# FMC_ADC_top.net
KiCad netlist of a schematic drawn in Altium Designer
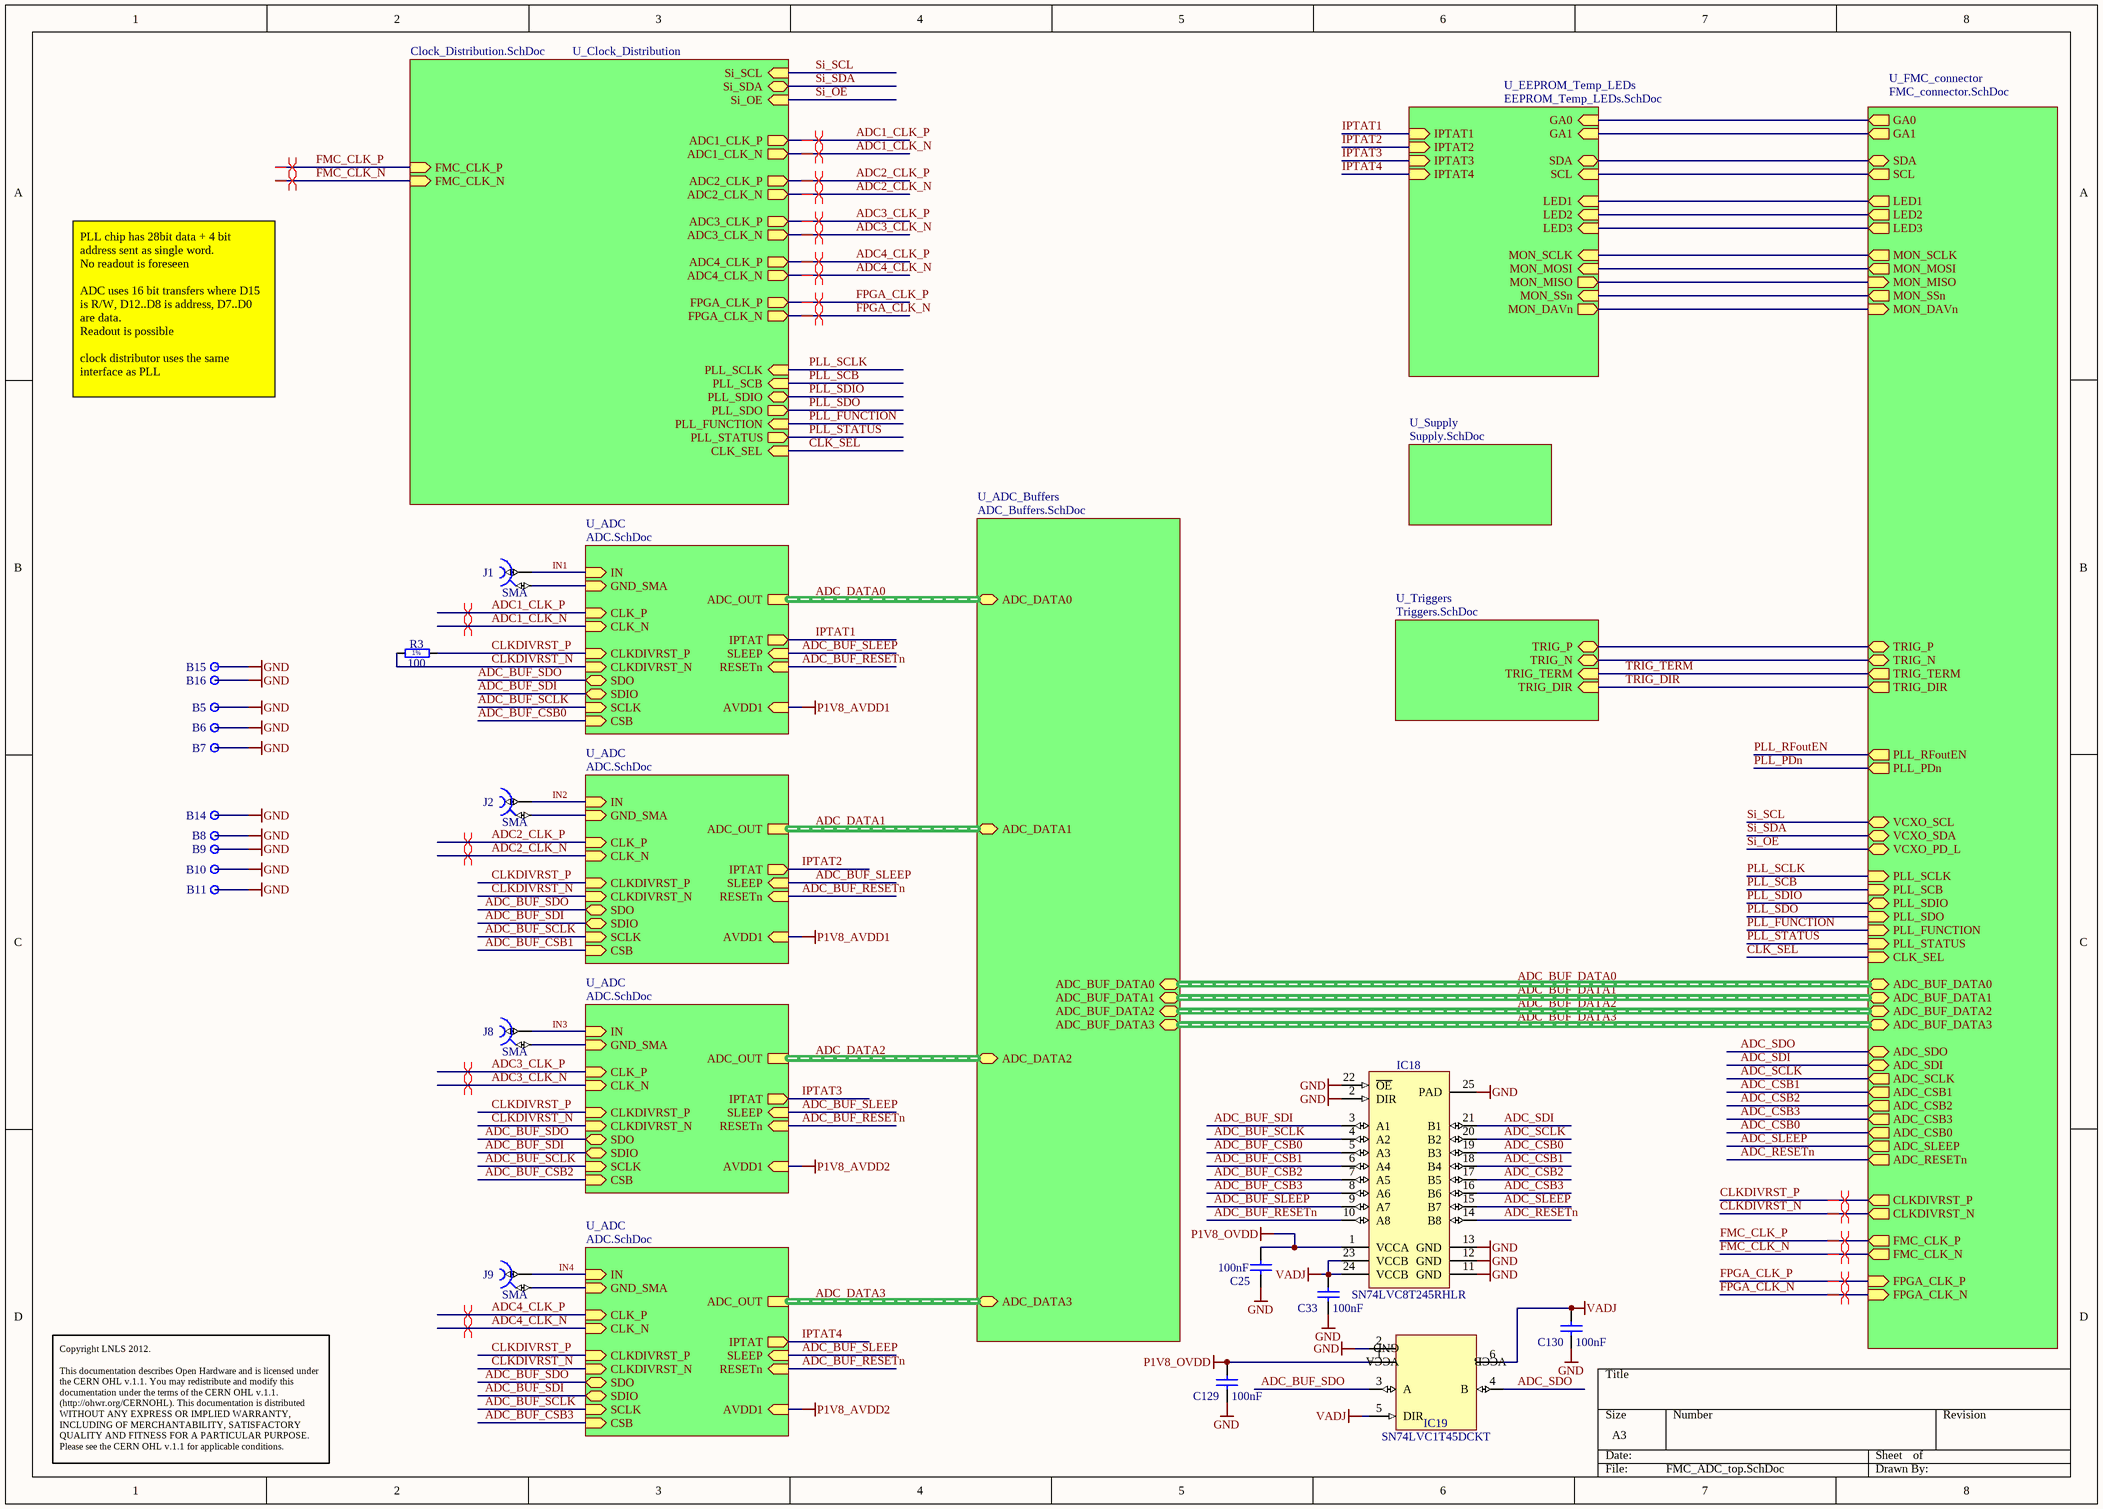
[diagram p0: FMC_ADC_top.SchDoc]

(export (version "E")
  (design (tool "Eeschema 10.0.6"))
  (components
    (comp (ref "B5")
      (value "Plated Hole")
      (footprint "MTG240_400_M")
      (description "Single Terminal Socket")
      (fields (field (name "PART NUMBER") "PLATED_HOLE2.4_PAD4.0_M") (field (name "AUTHOR") "LNLS DIG FCS"))
      (libsource (lib "Eletro-mechanical_LNLS") (part "Single Terminal Socket"))
    )
    (comp (ref "B6")
      (value "Plated Hole")
      (footprint "MTG240_400_M")
      (description "Single Terminal Socket")
      (fields (field (name "PART NUMBER") "PLATED_HOLE2.4_PAD4.0_M") (field (name "AUTHOR") "LNLS DIG FCS"))
      (libsource (lib "Eletro-mechanical_LNLS") (part "Single Terminal Socket"))
    )
    (comp (ref "B7")
      (value "Plated Hole")
      (footprint "MTG240_400_M")
      (description "Single Terminal Socket")
      (fields (field (name "PART NUMBER") "PLATED_HOLE2.4_PAD4.0_M") (field (name "AUTHOR") "LNLS DIG FCS"))
      (libsource (lib "Eletro-mechanical_LNLS") (part "Single Terminal Socket"))
    )
    (comp (ref "B8")
      (value "Plated Hole")
      (footprint "MTG240_400_M")
      (description "Single Terminal Socket")
      (fields (field (name "PART NUMBER") "PLATED_HOLE2.4_PAD4.0_M") (field (name "AUTHOR") "LNLS DIG FCS"))
      (libsource (lib "Eletro-mechanical_LNLS") (part "Single Terminal Socket"))
    )
    (comp (ref "B9")
      (value "Plated Hole")
      (footprint "MTG240_400_M")
      (description "Single Terminal Socket")
      (fields (field (name "PART NUMBER") "PLATED_HOLE2.4_PAD4.0_M") (field (name "AUTHOR") "LNLS DIG FCS"))
      (libsource (lib "Eletro-mechanical_LNLS") (part "Single Terminal Socket"))
    )
    (comp (ref "B10")
      (value "Plated Hole")
      (footprint "MTG240_400_M")
      (description "Single Terminal Socket")
      (fields (field (name "PART NUMBER") "PLATED_HOLE2.4_PAD4.0_M") (field (name "AUTHOR") "LNLS DIG FCS"))
      (libsource (lib "Eletro-mechanical_LNLS") (part "Single Terminal Socket"))
    )
    (comp (ref "B11")
      (value "Plated Hole")
      (footprint "MTG240_400_M")
      (description "Single Terminal Socket")
      (fields (field (name "PART NUMBER") "PLATED_HOLE2.4_PAD4.0_M") (field (name "AUTHOR") "LNLS DIG FCS"))
      (libsource (lib "Eletro-mechanical_LNLS") (part "Single Terminal Socket"))
    )
    (comp (ref "B14")
      (value "Plated Hole")
      (footprint "MTG240_400_M")
      (description "Single Terminal Socket")
      (fields (field (name "PART NUMBER") "PLATED_HOLE2.4_PAD4.0_M") (field (name "AUTHOR") "LNLS DIG FCS"))
      (libsource (lib "Eletro-mechanical_LNLS") (part "Single Terminal Socket"))
    )
    (comp (ref "B15")
      (value "Plated Hole")
      (footprint "MTG240_400_M")
      (description "Single Terminal Socket")
      (fields (field (name "PART NUMBER") "PLATED_HOLE2.4_PAD4.0_M") (field (name "AUTHOR") "LNLS DIG FCS"))
      (libsource (lib "Eletro-mechanical_LNLS") (part "Single Terminal Socket"))
    )
    (comp (ref "B16")
      (value "Plated Hole")
      (footprint "MTG240_400_M")
      (description "Single Terminal Socket")
      (fields (field (name "PART NUMBER") "PLATED_HOLE2.4_PAD4.0_M") (field (name "AUTHOR") "LNLS DIG FCS"))
      (libsource (lib "Eletro-mechanical_LNLS") (part "Single Terminal Socket"))
    )
    (comp (ref "C25")
      (value "100nF")
      (footprint "CAPC0603X33N")
      (description "Non-polarised capacitor")
      (fields
        (field (name "PART NUMBER") "CC0201_100NF_6.3V_10%_X5R")
        (field (name "VOLTAGE") "6.3V")
        (field (name "AUTHOR") "CERN DEM JLC")
      )
      (libsource (lib "Capacitors") (part "Capacitor - non polarized"))
    )
    (comp (ref "C33")
      (value "100nF")
      (footprint "CAPC0603X33N")
      (description "Non-polarised capacitor")
      (fields
        (field (name "PART NUMBER") "CC0201_100NF_6.3V_10%_X5R")
        (field (name "VOLTAGE") "6.3V")
        (field (name "AUTHOR") "CERN DEM JLC")
      )
      (libsource (lib "Capacitors") (part "Capacitor - non polarized"))
    )
    (comp (ref "C129")
      (value "100nF")
      (footprint "CAPC0603X33N")
      (description "Non-polarised capacitor")
      (fields
        (field (name "PART NUMBER") "CC0201_100NF_6.3V_10%_X5R")
        (field (name "VOLTAGE") "6.3V")
        (field (name "AUTHOR") "CERN DEM JLC")
      )
      (libsource (lib "Capacitors") (part "Capacitor - non polarized"))
    )
    (comp (ref "C130")
      (value "100nF")
      (footprint "CAPC0603X33N")
      (description "Non-polarised capacitor")
      (fields
        (field (name "PART NUMBER") "CC0201_100NF_6.3V_10%_X5R")
        (field (name "VOLTAGE") "6.3V")
        (field (name "AUTHOR") "CERN DEM JLC")
      )
      (libsource (lib "Capacitors") (part "Capacitor - non polarized"))
    )
    (comp (ref "IC18")
      (value "SN74LVC8T245RHLR")
      (footprint "QFN50P350X550X100-24N")
      (description "8-Bit Dual-Supply Bus Transceiver With Configurable Voltage Translation and 3-State Outputs")
      (fields (field (name "MANUFACTURER") "TEXAS INSTRUMENTS") (field (name "AUTHOR") "LNLS DIG GBMB"))
      (libsource (lib "ICs And Semiconductors_LNLS") (part "748T245"))
    )
    (comp (ref "IC19")
      (value "SN74LVC1T45DCKT")
      (footprint "SOT65P210X110-6N")
      (description "Single-Bit Dual-Supply Bus Transceiver")
      (fields (field (name "MANUFACTURER") "TEXAS INSTRUMENTS") (field (name "AUTHOR") "CERN DEM JLC"))
      (libsource (lib "ICs And Semiconductors") (part "741T45"))
    )
    (comp (ref "J1")
      (value "SMA")
      (footprint "AMPHENOL_901-143_IN BOARD")
      (fields
        (field (name "PART NUMBER") "AMPHENOL_901-143")
        (field (name "MANUFACTURER") "AMPHENOL")
        (field (name "MANUFACTURER PART NUMBER") "901-143")
        (field (name "AUTHOR") "LNLS DIG GBMB")
      )
      (libsource (lib "Connectors_LNLS") (part "Coax_1Female_1Shield"))
    )
    (comp (ref "J2")
      (value "SMA")
      (footprint "AMPHENOL_901-143_IN BOARD")
      (fields
        (field (name "PART NUMBER") "AMPHENOL_901-143")
        (field (name "MANUFACTURER") "AMPHENOL")
        (field (name "MANUFACTURER PART NUMBER") "901-143")
        (field (name "AUTHOR") "LNLS DIG GBMB")
      )
      (libsource (lib "Connectors_LNLS") (part "Coax_1Female_1Shield"))
    )
    (comp (ref "J8")
      (value "SMA")
      (footprint "AMPHENOL_901-143_IN BOARD")
      (fields
        (field (name "PART NUMBER") "AMPHENOL_901-143")
        (field (name "MANUFACTURER") "AMPHENOL")
        (field (name "MANUFACTURER PART NUMBER") "901-143")
        (field (name "AUTHOR") "LNLS DIG GBMB")
      )
      (libsource (lib "Connectors_LNLS") (part "Coax_1Female_1Shield"))
    )
    (comp (ref "J9")
      (value "SMA")
      (footprint "AMPHENOL_901-143_IN BOARD")
      (fields
        (field (name "PART NUMBER") "AMPHENOL_901-143")
        (field (name "MANUFACTURER") "AMPHENOL")
        (field (name "MANUFACTURER PART NUMBER") "901-143")
        (field (name "AUTHOR") "LNLS DIG GBMB")
      )
      (libsource (lib "Connectors_LNLS") (part "Coax_1Female_1Shield"))
    )
    (comp (ref "R3")
      (value "100")
      (footprint "RESC1005X40N")
      (description "Resistor - 1%")
      (fields
        (field (name "PART NUMBER") "R0402_100R_1%_0.0625W_100PPM")
        (field (name "POWER") "0.0625W")
        (field (name "AUTHOR") "CERN DEM JLC")
      )
      (libsource (lib "Resistors") (part "Resistor - 1%"))
    )
  )
  (nets
    (net (code "17") (name "/ADC_BUF_CSB0") (class "Default")
      (node (ref "IC18") (pin "5") (pinfunction "A3_5") (pintype "bidirectional"))
    )
    (net (code "18") (name "/ADC_BUF_CSB1") (class "Default")
      (node (ref "IC18") (pin "6") (pinfunction "A4_6") (pintype "bidirectional"))
    )
    (net (code "19") (name "/ADC_BUF_CSB2") (class "Default")
      (node (ref "IC18") (pin "7") (pinfunction "A5_7") (pintype "bidirectional"))
    )
    (net (code "20") (name "/ADC_BUF_CSB3") (class "Default")
      (node (ref "IC18") (pin "8") (pinfunction "A6_8") (pintype "bidirectional"))
    )
    (net (code "21") (name "/ADC_BUF_RESETn") (class "Default")
      (node (ref "IC18") (pin "10") (pinfunction "A8_10") (pintype "bidirectional"))
    )
    (net (code "22") (name "/ADC_BUF_SCLK") (class "Default")
      (node (ref "IC18") (pin "4") (pinfunction "A2_4") (pintype "bidirectional"))
    )
    (net (code "23") (name "/ADC_BUF_SDI") (class "Default")
      (node (ref "IC18") (pin "3") (pinfunction "A1_3") (pintype "bidirectional"))
    )
    (net (code "24") (name "/ADC_BUF_SDO") (class "Default")
      (node (ref "IC19") (pin "3") (pinfunction "A_3") (pintype "bidirectional"))
    )
    (net (code "25") (name "/ADC_BUF_SLEEP") (class "Default")
      (node (ref "IC18") (pin "9") (pinfunction "A7_9") (pintype "bidirectional"))
    )
    (net (code "26") (name "/ADC_CSB0") (class "Default")
      (node (ref "IC18") (pin "19") (pinfunction "B3_19") (pintype "bidirectional"))
    )
    (net (code "27") (name "/ADC_CSB1") (class "Default")
      (node (ref "IC18") (pin "18") (pinfunction "B4_18") (pintype "bidirectional"))
    )
    (net (code "28") (name "/ADC_CSB2") (class "Default")
      (node (ref "IC18") (pin "17") (pinfunction "B5_17") (pintype "bidirectional"))
    )
    (net (code "29") (name "/ADC_CSB3") (class "Default")
      (node (ref "IC18") (pin "16") (pinfunction "B6_16") (pintype "bidirectional"))
    )
    (net (code "30") (name "/ADC_RESETn") (class "Default")
      (node (ref "IC18") (pin "14") (pinfunction "B8_14") (pintype "bidirectional"))
    )
    (net (code "31") (name "/ADC_SCLK") (class "Default")
      (node (ref "IC18") (pin "20") (pinfunction "B2_20") (pintype "bidirectional"))
    )
    (net (code "32") (name "/ADC_SDI") (class "Default")
      (node (ref "IC18") (pin "21") (pinfunction "B1_21") (pintype "bidirectional"))
    )
    (net (code "33") (name "/ADC_SDO") (class "Default")
      (node (ref "IC19") (pin "4") (pinfunction "B_4") (pintype "bidirectional"))
    )
    (net (code "34") (name "/ADC_SLEEP") (class "Default")
      (node (ref "IC18") (pin "15") (pinfunction "B7_15") (pintype "bidirectional"))
    )
    (net (code "35") (name "/CLKDIVRST_N") (class "Default")
      (node (ref "R3") (pin "1") (pinfunction "1_1") (pintype "passive"))
    )
    (net (code "36") (name "/CLKDIVRST_P") (class "Default")
      (node (ref "R3") (pin "2") (pinfunction "2_2") (pintype "passive"))
    )
    (net (code "44") (name "/GND_SMA") (class "Default")
      (node (ref "J9") (pin "2") (pinfunction "2_2") (pintype "bidirectional"))
    )
    (net (code "45") (name "/GND_SMA_1") (class "Default")
      (node (ref "J2") (pin "2") (pinfunction "2_2") (pintype "bidirectional"))
    )
    (net (code "46") (name "/GND_SMA_2") (class "Default")
      (node (ref "J1") (pin "2") (pinfunction "2_2") (pintype "bidirectional"))
    )
    (net (code "47") (name "/GND_SMA_3") (class "Default")
      (node (ref "J8") (pin "2") (pinfunction "2_2") (pintype "bidirectional"))
    )
    (net (code "48") (name "/IN1") (class "Default")
      (node (ref "J1") (pin "1") (pinfunction "1_1") (pintype "bidirectional"))
    )
    (net (code "49") (name "/IN2") (class "Default")
      (node (ref "J2") (pin "1") (pinfunction "1_1") (pintype "bidirectional"))
    )
    (net (code "50") (name "/IN3") (class "Default")
      (node (ref "J8") (pin "1") (pinfunction "1_1") (pintype "bidirectional"))
    )
    (net (code "51") (name "/IN4") (class "Default")
      (node (ref "J9") (pin "1") (pinfunction "1_1") (pintype "bidirectional"))
    )
    (net (code "89") (name "GND") (class "Default")
      (node (ref "B10") (pin "1") (pinfunction "1_1") (pintype "bidirectional"))
      (node (ref "B11") (pin "1") (pinfunction "1_1") (pintype "bidirectional"))
      (node (ref "B14") (pin "1") (pinfunction "1_1") (pintype "bidirectional"))
      (node (ref "B15") (pin "1") (pinfunction "1_1") (pintype "bidirectional"))
      (node (ref "B16") (pin "1") (pinfunction "1_1") (pintype "bidirectional"))
      (node (ref "B5") (pin "1") (pinfunction "1_1") (pintype "bidirectional"))
      (node (ref "B6") (pin "1") (pinfunction "1_1") (pintype "bidirectional"))
      (node (ref "B7") (pin "1") (pinfunction "1_1") (pintype "bidirectional"))
      (node (ref "B8") (pin "1") (pinfunction "1_1") (pintype "bidirectional"))
      (node (ref "B9") (pin "1") (pinfunction "1_1") (pintype "bidirectional"))
      (node (ref "C129") (pin "1") (pinfunction "1_1") (pintype "passive"))
      (node (ref "C130") (pin "1") (pinfunction "1_1") (pintype "passive"))
      (node (ref "C25") (pin "2") (pinfunction "2_2") (pintype "passive"))
      (node (ref "C33") (pin "1") (pinfunction "1_1") (pintype "passive"))
      (node (ref "IC18") (pin "11") (pinfunction "GND_11") (pintype "power_in"))
      (node (ref "IC18") (pin "12") (pinfunction "GND_12") (pintype "power_in"))
      (node (ref "IC18") (pin "13") (pinfunction "GND_13") (pintype "power_in"))
      (node (ref "IC18") (pin "2") (pinfunction "DIR_2") (pintype "input"))
      (node (ref "IC18") (pin "22") (pinfunction "~{OE}_22") (pintype "input"))
      (node (ref "IC18") (pin "25") (pinfunction "PAD_25") (pintype "power_in"))
      (node (ref "IC19") (pin "2") (pinfunction "GND_2") (pintype "power_in"))
    )
    (net (code "92") (name "P1V8_OVDD") (class "Default")
      (node (ref "C129") (pin "2") (pinfunction "2_2") (pintype "passive"))
      (node (ref "C25") (pin "1") (pinfunction "1_1") (pintype "passive"))
      (node (ref "IC18") (pin "1") (pinfunction "VCCA_1") (pintype "power_in"))
      (node (ref "IC19") (pin "1") (pinfunction "VCCA_1") (pintype "power_in"))
    )
    (net (code "93") (name "VADJ") (class "Default")
      (node (ref "C130") (pin "2") (pinfunction "2_2") (pintype "passive"))
      (node (ref "C33") (pin "2") (pinfunction "2_2") (pintype "passive"))
      (node (ref "IC18") (pin "23") (pinfunction "VCCB_23") (pintype "power_in"))
      (node (ref "IC18") (pin "24") (pinfunction "VCCB_24") (pintype "power_in"))
      (node (ref "IC19") (pin "5") (pinfunction "DIR_5") (pintype "input"))
      (node (ref "IC19") (pin "6") (pinfunction "VCCB_6") (pintype "power_in"))
    )
  )
)
